# FAT32.net
KiCad netlist of a schematic drawn in Altium Designer
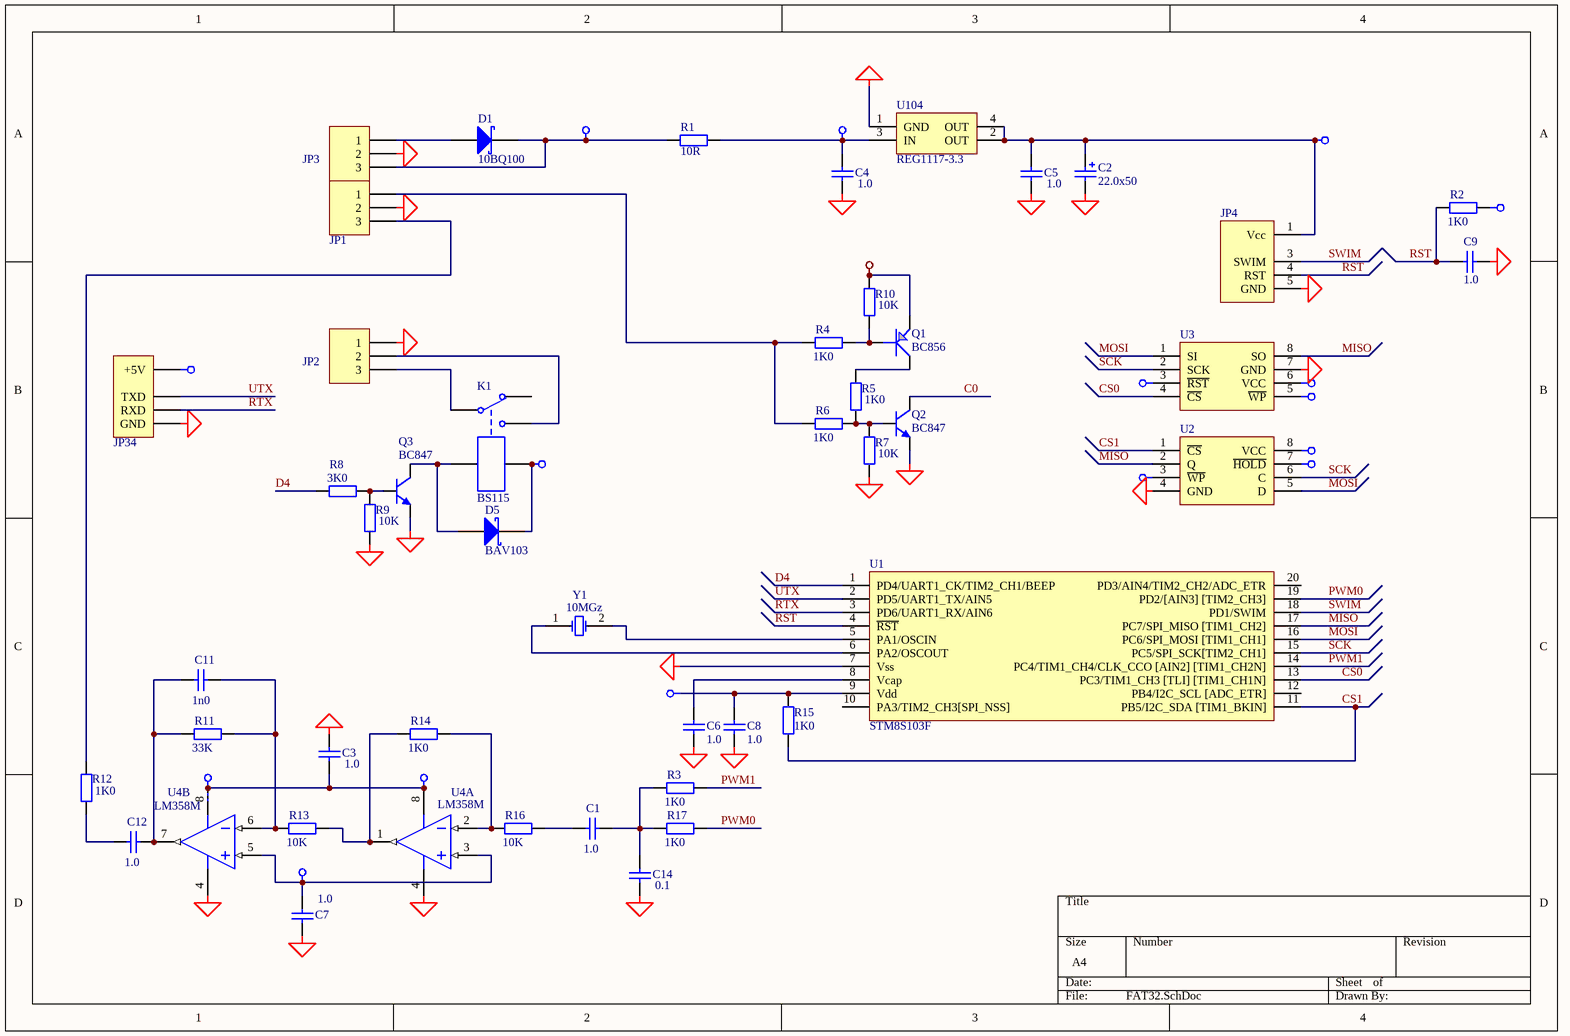
[diagram p0: FAT32.SchDoc]

(export (version "E")
  (design (tool "Eeschema 10.0.6"))
  (components
    (comp (ref "C1")
      (value "1.0")
      (footprint "_1206")
      (description "Capacitor (Semiconductor SIM Model)")
      (fields (field (name "MANUFACTURER") "Generic Components") (field (name "PUBLISHER") "Altium Limited"))
      (libsource (lib "Miscellaneous Devices") (part "Cap Semi"))
    )
    (comp (ref "C2")
      (value "22.0x50")
      (footprint "CAP_EL_6_3")
      (description "Polarized Capacitor (Radial)")
      (fields (field (name "MANUFACTURER") "Generic Components") (field (name "PUBLISHER") "Altium Limited"))
      (libsource (lib "PAL") (part "Cap Pol1"))
    )
    (comp (ref "C3")
      (value "1.0")
      (footprint "_1206")
      (description "Capacitor (Semiconductor SIM Model)")
      (fields (field (name "MANUFACTURER") "Generic Components") (field (name "PUBLISHER") "Altium Limited"))
      (libsource (lib "Miscellaneous Devices") (part "Cap Semi"))
    )
    (comp (ref "C4")
      (value "1.0")
      (footprint "_1206")
      (description "Capacitor (Semiconductor SIM Model)")
      (fields (field (name "MANUFACTURER") "Generic Components") (field (name "PUBLISHER") "Altium Limited"))
      (libsource (lib "Miscellaneous Devices") (part "Cap Semi"))
    )
    (comp (ref "C5")
      (value "1.0")
      (footprint "_1206")
      (description "Capacitor (Semiconductor SIM Model)")
      (fields (field (name "MANUFACTURER") "Generic Components") (field (name "PUBLISHER") "Altium Limited"))
      (libsource (lib "Miscellaneous Devices") (part "Cap Semi"))
    )
    (comp (ref "C6")
      (value "1.0")
      (footprint "_1206")
      (description "Capacitor (Semiconductor SIM Model)")
      (fields (field (name "MANUFACTURER") "Generic Components") (field (name "PUBLISHER") "Altium Limited"))
      (libsource (lib "Miscellaneous Devices") (part "Cap Semi"))
    )
    (comp (ref "C7")
      (value "1.0")
      (footprint "_1206")
      (description "Capacitor (Semiconductor SIM Model)")
      (fields (field (name "MANUFACTURER") "Generic Components") (field (name "PUBLISHER") "Altium Limited"))
      (libsource (lib "Miscellaneous Devices") (part "Cap Semi"))
    )
    (comp (ref "C8")
      (value "1.0")
      (footprint "_1206")
      (description "Capacitor (Semiconductor SIM Model)")
      (fields (field (name "MANUFACTURER") "Generic Components") (field (name "PUBLISHER") "Altium Limited"))
      (libsource (lib "Miscellaneous Devices") (part "Cap Semi"))
    )
    (comp (ref "C9")
      (value "1.0")
      (footprint "_1206")
      (description "Capacitor (Semiconductor SIM Model)")
      (fields (field (name "MANUFACTURER") "Generic Components") (field (name "PUBLISHER") "Altium Limited"))
      (libsource (lib "") (part "Cap Semi_1"))
    )
    (comp (ref "C11")
      (value "1n0")
      (footprint "_1206")
      (description "Capacitor (Semiconductor SIM Model)")
      (fields (field (name "MANUFACTURER") "Generic Components") (field (name "PUBLISHER") "Altium Limited"))
      (libsource (lib "") (part "Cap Semi_1"))
    )
    (comp (ref "C12")
      (value "1.0")
      (footprint "_1206")
      (description "Capacitor (Semiconductor SIM Model)")
      (fields (field (name "MANUFACTURER") "Generic Components") (field (name "PUBLISHER") "Altium Limited"))
      (libsource (lib "") (part "Cap Semi_1"))
    )
    (comp (ref "C14")
      (value "0.1")
      (footprint "_1206")
      (description "Capacitor (Semiconductor SIM Model)")
      (fields (field (name "MANUFACTURER") "Generic Components") (field (name "PUBLISHER") "Altium Limited"))
      (libsource (lib "Miscellaneous Devices") (part "Cap Semi"))
    )
    (comp (ref "D1")
      (value "10BQ100")
      (footprint "DSO-C2/X2.3")
      (description "Schottky Rectifier")
      (fields
        (field (name "MANUFACTURER") "International Rectifier")
        (field (name "PUBLISHER") "Altium Limited")
      )
      (libsource (lib "IR Discrete Diode") (part "10BQ015"))
    )
    (comp (ref "D5")
      (value "BAV103")
      (footprint "_1206d")
      (description "Schottky Rectifier")
      (fields
        (field (name "MANUFACTURER") "International Rectifier")
        (field (name "PUBLISHER") "Altium Limited")
      )
      (libsource (lib "IR Discrete Diode") (part "10BQ015"))
    )
    (comp (ref "JP1")
      (value "Header 3")
      (footprint "BT5-3")
      (description "Header, 3-Pin")
      (fields (field (name "MANUFACTURER") "Generic Components") (field (name "PUBLISHER") "Altium Limited"))
      (libsource (lib "Miscellaneous Connectors") (part "Header 3"))
    )
    (comp (ref "JP2")
      (value "Header 3")
      (footprint "BT5-3")
      (description "Header, 3-Pin")
      (fields (field (name "MANUFACTURER") "Generic Components") (field (name "PUBLISHER") "Altium Limited"))
      (libsource (lib "Miscellaneous Connectors") (part "Header 3"))
    )
    (comp (ref "JP3")
      (value "Header 3")
      (footprint "BT5-3")
      (description "Header, 3-Pin")
      (fields (field (name "MANUFACTURER") "Generic Components") (field (name "PUBLISHER") "Altium Limited"))
      (libsource (lib "Miscellaneous Connectors") (part "Header 3"))
    )
    (comp (ref "JP4") (value "~") (footprint "HDR1X5_uart") (libsource (lib "PAL") (part "SWIM_CONN")))
    (comp (ref "JP34")
      (value "UART_PORT")
      (footprint "HDR1X5_uart")
      (description "Header, 5-Pin")
      (fields (field (name "MANUFACTURER") "Generic Components") (field (name "PUBLISHER") "Altium Limited"))
      (libsource (lib "igorenja") (part "UART_PORT"))
    )
    (comp (ref "K1")
      (value "BS115")
      (footprint "BS115")
      (description "Single-Pole Dual-Throw Relay")
      (fields (field (name "MANUFACTURER") "Generic Components") (field (name "PUBLISHER") "Altium Limited"))
      (libsource (lib "PAL") (part "BS115"))
    )
    (comp (ref "Q1") (value "BC856") (footprint "SO-G3") (libsource (lib "MAIN") (part "GT109")))
    (comp (ref "Q2")
      (value "BC847")
      (footprint "SO-G3/C2.5")
      (description "General Purpose Transistor NPN Silicon")
      (fields (field (name "MANUFACTURER") "Motorola") (field (name "PUBLISHER") "Altium Limited"))
      (libsource (lib "PAL") (part "BC847ALT1"))
    )
    (comp (ref "Q3")
      (value "BC847")
      (footprint "SO-G3/C2.5")
      (description "General Purpose Transistor NPN Silicon")
      (fields (field (name "MANUFACTURER") "Motorola") (field (name "PUBLISHER") "Altium Limited"))
      (libsource (lib "PAL") (part "BC847ALT1"))
    )
    (comp (ref "R1")
      (value "Res2")
      (footprint "_1206")
      (description "Resistor")
      (fields
        (field (name "MANUFACTURER") "Generic Components")
        (field (name "ALTIUM_VALUE") "10R")
        (field (name "PUBLISHER") "Altium Limited")
      )
      (libsource (lib "") (part "Res2_1"))
    )
    (comp (ref "R2")
      (value "1K0")
      (footprint "_1206")
      (description "Resistor")
      (fields (field (name "MANUFACTURER") "Generic Components") (field (name "PUBLISHER") "Altium Limited"))
      (libsource (lib "") (part "Res2_3"))
    )
    (comp (ref "R3")
      (value "1K0")
      (footprint "_1206")
      (description "Resistor")
      (fields (field (name "MANUFACTURER") "Generic Components") (field (name "PUBLISHER") "Altium Limited"))
      (libsource (lib "Miscellaneous Devices") (part "Res2"))
    )
    (comp (ref "R4")
      (value "1K0")
      (footprint "_1206")
      (description "Resistor")
      (fields (field (name "MANUFACTURER") "Generic Components") (field (name "PUBLISHER") "Altium Limited"))
      (libsource (lib "") (part "Res2_3"))
    )
    (comp (ref "R5")
      (value "1K0")
      (footprint "_1206")
      (description "Resistor")
      (fields (field (name "MANUFACTURER") "Generic Components") (field (name "PUBLISHER") "Altium Limited"))
      (libsource (lib "") (part "Res2_5"))
    )
    (comp (ref "R6")
      (value "1K0")
      (footprint "_1206")
      (description "Resistor")
      (fields (field (name "MANUFACTURER") "Generic Components") (field (name "PUBLISHER") "Altium Limited"))
      (libsource (lib "") (part "Res2_3"))
    )
    (comp (ref "R7")
      (value "10K")
      (footprint "_1206")
      (description "Resistor")
      (fields (field (name "MANUFACTURER") "Generic Components") (field (name "PUBLISHER") "Altium Limited"))
      (libsource (lib "") (part "Res2_2"))
    )
    (comp (ref "R8")
      (value "3K0")
      (footprint "_1206")
      (description "Resistor")
      (fields (field (name "MANUFACTURER") "Generic Components") (field (name "PUBLISHER") "Altium Limited"))
      (libsource (lib "") (part "Res2_3"))
    )
    (comp (ref "R9")
      (value "10K")
      (footprint "_1206")
      (description "Resistor")
      (fields (field (name "MANUFACTURER") "Generic Components") (field (name "PUBLISHER") "Altium Limited"))
      (libsource (lib "") (part "Res2_2"))
    )
    (comp (ref "R10")
      (value "10K")
      (footprint "_1206")
      (description "Resistor")
      (fields (field (name "MANUFACTURER") "Generic Components") (field (name "PUBLISHER") "Altium Limited"))
      (libsource (lib "PAL") (part "RES"))
    )
    (comp (ref "R11")
      (value "33K")
      (footprint "_1206")
      (description "Resistor")
      (fields (field (name "MANUFACTURER") "Generic Components") (field (name "PUBLISHER") "Altium Limited"))
      (libsource (lib "Miscellaneous Devices") (part "Res2"))
    )
    (comp (ref "R12")
      (value "1K0")
      (footprint "_1206")
      (description "Resistor")
      (fields (field (name "MANUFACTURER") "Generic Components") (field (name "PUBLISHER") "Altium Limited"))
      (libsource (lib "") (part "Res2_5"))
    )
    (comp (ref "R13")
      (value "10K")
      (footprint "_1206")
      (description "Resistor")
      (fields (field (name "MANUFACTURER") "Generic Components") (field (name "PUBLISHER") "Altium Limited"))
      (libsource (lib "Miscellaneous Devices") (part "Res2"))
    )
    (comp (ref "R14")
      (value "1K0")
      (footprint "_1206")
      (description "Resistor")
      (fields (field (name "MANUFACTURER") "Generic Components") (field (name "PUBLISHER") "Altium Limited"))
      (libsource (lib "Miscellaneous Devices") (part "Res2"))
    )
    (comp (ref "R15")
      (value "1K0")
      (footprint "_1206")
      (description "Resistor")
      (fields (field (name "MANUFACTURER") "Generic Components") (field (name "PUBLISHER") "Altium Limited"))
      (libsource (lib "") (part "Res2_4"))
    )
    (comp (ref "R16")
      (value "10K")
      (footprint "_1206")
      (description "Resistor")
      (fields (field (name "MANUFACTURER") "Generic Components") (field (name "PUBLISHER") "Altium Limited"))
      (libsource (lib "Miscellaneous Devices") (part "Res2"))
    )
    (comp (ref "R17")
      (value "1K0")
      (footprint "_1206")
      (description "Resistor")
      (fields (field (name "MANUFACTURER") "Generic Components") (field (name "PUBLISHER") "Altium Limited"))
      (libsource (lib "Miscellaneous Devices") (part "Res2"))
    )
    (comp (ref "U1") (value "~") (footprint "TSSO6x6-G20/Y1.6") (libsource (lib "PAL") (part "STM8S103F")))
    (comp (ref "U2") (value "~") (footprint "SO-G8") (libsource (lib "PAL") (part "M25P10")))
    (comp (ref "U3") (value "~") (footprint "AT45W") (libsource (lib "PAL") (part "AT45DB161D-SU")))
    (comp (ref "U4")
      (value "LM358M")
      (footprint "SO-G8")
      (description "Low-Power Dual Operational Amplifier")
      (fields
        (field (name "MANUFACTURER") "National Semiconductor")
        (field (name "PUBLISHER") "Altium Limited")
      )
      (libsource (lib "NSC Operational Amplifier") (part "LM358M"))
    )
    (comp (ref "U104")
      (value "REG1117-3.3")
      (footprint "SIP-G3/C7.4")
      (description "800mA and 1A Low Dropout Positive Regulator 2.85V, 3.3V, 5V, and Adjustable")
      (fields (field (name "MANUFACTURER") "Burr-Brown") (field (name "PUBLISHER") "Altium Limited"))
      (libsource (lib "BB Power Mgt Voltage Regulator") (part "REG1117-3.3"))
    )
    (comp (ref "Y1")
      (value "10MGz")
      (footprint "QWARZ1")
      (description "Crystal Oscillator")
      (fields (field (name "MANUFACTURER") "Generic Components") (field (name "PUBLISHER") "Altium Limited"))
      (libsource (lib "Miscellaneous Devices") (part "XTAL"))
    )
  )
  (nets
    (net (code "1") (name "+3v3") (class "Default")
      (node (ref "C2") (pin "1") (pinfunction "1_1") (pintype "passive"))
      (node (ref "C5") (pin "2") (pinfunction "2_2") (pintype "passive"))
      (node (ref "C7") (pin "2") (pinfunction "2_2") (pintype "passive"))
      (node (ref "C8") (pin "2") (pinfunction "2_2") (pintype "passive"))
      (node (ref "JP34") (pin "1") (pinfunction "+5V_1") (pintype "passive"))
      (node (ref "JP4") (pin "1") (pinfunction "Vcc_1") (pintype "passive"))
      (node (ref "R15") (pin "2") (pinfunction "2_2") (pintype "passive"))
      (node (ref "R2") (pin "1") (pinfunction "1_1") (pintype "passive"))
      (node (ref "U1") (pin "9") (pinfunction "Vdd_9") (pintype "passive"))
      (node (ref "U104") (pin "2") (pinfunction "OUT_2") (pintype "power_in"))
      (node (ref "U104") (pin "4") (pinfunction "OUT_4") (pintype "power_in"))
      (node (ref "U2") (pin "3") (pinfunction "~{WP}_3") (pintype "passive"))
      (node (ref "U2") (pin "7") (pinfunction "~{HOLD}_7") (pintype "passive"))
      (node (ref "U2") (pin "8") (pinfunction "VCC_8") (pintype "passive"))
      (node (ref "U3") (pin "3") (pinfunction "~{RST}_3") (pintype "passive"))
      (node (ref "U3") (pin "5") (pinfunction "~{WP}_5") (pintype "passive"))
      (node (ref "U3") (pin "6") (pinfunction "VCC_6") (pintype "passive"))
      (node (ref "U4") (pin "3") (pinfunction "IN+_3") (pintype "input"))
      (node (ref "U4") (pin "5") (pinfunction "IN+_5") (pintype "input"))
    )
    (net (code "2") (name "+12v") (class "Default")
      (node (ref "D1") (pin "2") (pinfunction "K_2") (pintype "passive"))
      (node (ref "D5") (pin "2") (pinfunction "K_2") (pintype "passive"))
      (node (ref "JP3") (pin "3") (pinfunction "3_3") (pintype "passive"))
      (node (ref "K1") (pin "5") (pinfunction "5_5") (pintype "passive"))
      (node (ref "Q1") (pin "2") (pinfunction "E_2") (pintype "passive"))
      (node (ref "R1") (pin "1") (pinfunction "1_1") (pintype "passive"))
      (node (ref "R10") (pin "2") (pinfunction "2_2") (pintype "passive"))
    )
    (net (code "3") (name "+12vi") (class "Default")
      (node (ref "C3") (pin "2") (pinfunction "2_2") (pintype "passive"))
      (node (ref "C4") (pin "2") (pinfunction "2_2") (pintype "passive"))
      (node (ref "R1") (pin "2") (pinfunction "2_2") (pintype "passive"))
      (node (ref "U104") (pin "3") (pinfunction "IN_3") (pintype "power_in"))
      (node (ref "U4") (pin "8") (pinfunction "V+_8") (pintype "power_in"))
    )
    (net (code "4") (name "/C0") (class "Default")
      (node (ref "Q2") (pin "3") (pinfunction "C_3") (pintype "passive"))
    )
    (net (code "5") (name "/CS0") (class "Default")
      (node (ref "U1") (pin "13") (pinfunction "PC3/TIM1_CH3_[TLI]_[TIM1_CH1N]_13") (pintype "passive"))
      (node (ref "U3") (pin "4") (pinfunction "~{CS}_4") (pintype "passive"))
    )
    (net (code "6") (name "/CS1") (class "Default")
      (node (ref "R15") (pin "1") (pinfunction "1_1") (pintype "passive"))
      (node (ref "U1") (pin "11") (pinfunction "PB5/I2C_SDA_[TIM1_BKIN]_11") (pintype "passive"))
      (node (ref "U2") (pin "1") (pinfunction "~{CS}_1") (pintype "passive"))
    )
    (net (code "7") (name "/D4") (class "Default")
      (node (ref "R8") (pin "2") (pinfunction "2_2") (pintype "passive"))
      (node (ref "U1") (pin "1") (pinfunction "PD4/UART1_CK/TIM2_CH1/BEEP_1") (pintype "passive"))
    )
    (net (code "8") (name "/MISO") (class "Default")
      (node (ref "U1") (pin "17") (pinfunction "PC7/SPI_MISO_[TIM1_CH2]_17") (pintype "passive"))
      (node (ref "U2") (pin "2") (pinfunction "Q_2") (pintype "passive"))
      (node (ref "U3") (pin "8") (pinfunction "SO_8") (pintype "passive"))
    )
    (net (code "9") (name "/MOSI") (class "Default")
      (node (ref "U1") (pin "16") (pinfunction "PC6/SPI_MOSI_[TIM1_CH1]_16") (pintype "passive"))
      (node (ref "U2") (pin "5") (pinfunction "D_5") (pintype "passive"))
      (node (ref "U3") (pin "1") (pinfunction "SI_1") (pintype "passive"))
    )
    (net (code "10") (name "/PWM0") (class "Default")
      (node (ref "R17") (pin "2") (pinfunction "2_2") (pintype "passive"))
      (node (ref "U1") (pin "19") (pinfunction "PD2/[AIN3]_[TIM2_CH3]_19") (pintype "passive"))
    )
    (net (code "11") (name "/PWM1") (class "Default")
      (node (ref "R3") (pin "2") (pinfunction "2_2") (pintype "passive"))
      (node (ref "U1") (pin "14") (pinfunction "PC4/TIM1_CH4/CLK_CCO_[AIN2]_[TIM1_CH2N]_14") (pintype "passive"))
    )
    (net (code "12") (name "/RST") (class "Default")
      (node (ref "C9") (pin "2") (pinfunction "2_2") (pintype "passive"))
      (node (ref "JP4") (pin "4") (pinfunction "RST_4") (pintype "passive"))
      (node (ref "R2") (pin "2") (pinfunction "2_2") (pintype "passive"))
      (node (ref "U1") (pin "4") (pinfunction "~{RST}_4") (pintype "passive"))
    )
    (net (code "13") (name "/RTX") (class "Default")
      (node (ref "JP34") (pin "4") (pinfunction "RXD_4") (pintype "passive"))
      (node (ref "U1") (pin "3") (pinfunction "PD6/UART1_RX/AIN6_3") (pintype "passive"))
    )
    (net (code "14") (name "/SCK") (class "Default")
      (node (ref "U1") (pin "15") (pinfunction "PC5/SPI_SCK[TIM2_CH1]_15") (pintype "passive"))
      (node (ref "U2") (pin "6") (pinfunction "C_6") (pintype "passive"))
      (node (ref "U3") (pin "2") (pinfunction "SCK_2") (pintype "passive"))
    )
    (net (code "15") (name "/SWIM") (class "Default")
      (node (ref "JP4") (pin "3") (pinfunction "SWIM_3") (pintype "passive"))
      (node (ref "U1") (pin "18") (pinfunction "PD1/SWIM_18") (pintype "passive"))
    )
    (net (code "16") (name "/UTX") (class "Default")
      (node (ref "JP34") (pin "3") (pinfunction "TXD_3") (pintype "passive"))
      (node (ref "U1") (pin "2") (pinfunction "PD5/UART1_TX/AIN5_2") (pintype "passive"))
    )
    (net (code "17") (name "GND") (class "Default")
      (node (ref "C14") (pin "2") (pinfunction "2_2") (pintype "passive"))
      (node (ref "C2") (pin "2") (pinfunction "2_2") (pintype "passive"))
      (node (ref "C3") (pin "1") (pinfunction "1_1") (pintype "passive"))
      (node (ref "C4") (pin "1") (pinfunction "1_1") (pintype "passive"))
      (node (ref "C5") (pin "1") (pinfunction "1_1") (pintype "passive"))
      (node (ref "C6") (pin "1") (pinfunction "1_1") (pintype "passive"))
      (node (ref "C7") (pin "1") (pinfunction "1_1") (pintype "passive"))
      (node (ref "C8") (pin "1") (pinfunction "1_1") (pintype "passive"))
      (node (ref "C9") (pin "1") (pinfunction "1_1") (pintype "passive"))
      (node (ref "JP1") (pin "2") (pinfunction "2_2") (pintype "passive"))
      (node (ref "JP2") (pin "1") (pinfunction "1_1") (pintype "passive"))
      (node (ref "JP3") (pin "2") (pinfunction "2_2") (pintype "passive"))
      (node (ref "JP34") (pin "5") (pinfunction "GND_5") (pintype "passive"))
      (node (ref "JP4") (pin "5") (pinfunction "GND_5") (pintype "passive"))
      (node (ref "Q2") (pin "2") (pinfunction "E_2") (pintype "passive"))
      (node (ref "Q3") (pin "2") (pinfunction "E_2") (pintype "passive"))
      (node (ref "R7") (pin "2") (pinfunction "2_2") (pintype "passive"))
      (node (ref "R9") (pin "2") (pinfunction "2_2") (pintype "passive"))
      (node (ref "U1") (pin "7") (pinfunction "Vss_7") (pintype "passive"))
      (node (ref "U104") (pin "1") (pinfunction "GND_1") (pintype "power_in"))
      (node (ref "U2") (pin "4") (pinfunction "GND_4") (pintype "passive"))
      (node (ref "U3") (pin "7") (pinfunction "GND_7") (pintype "passive"))
      (node (ref "U4") (pin "4") (pinfunction "GND_4") (pintype "power_in"))
    )
    (net (code "18") (name "Net-(C1-Pad1)") (class "Default")
      (node (ref "C1") (pin "1") (pinfunction "1_1") (pintype "passive"))
      (node (ref "R16") (pin "2") (pinfunction "2_2") (pintype "passive"))
    )
    (net (code "19") (name "Net-(C1-Pad2)") (class "Default")
      (node (ref "C1") (pin "2") (pinfunction "2_2") (pintype "passive"))
      (node (ref "C14") (pin "1") (pinfunction "1_1") (pintype "passive"))
      (node (ref "R17") (pin "1") (pinfunction "1_1") (pintype "passive"))
      (node (ref "R3") (pin "1") (pinfunction "1_1") (pintype "passive"))
    )
    (net (code "20") (name "Net-(C12-Pad2)") (class "Default")
      (node (ref "C12") (pin "2") (pinfunction "2_2") (pintype "passive"))
      (node (ref "R12") (pin "2") (pinfunction "2_2") (pintype "passive"))
    )
    (net (code "21") (name "Net-(D1-A)") (class "Default")
      (node (ref "D1") (pin "1") (pinfunction "A_1") (pintype "passive"))
      (node (ref "JP3") (pin "1") (pinfunction "1_1") (pintype "passive"))
    )
    (net (code "22") (name "Net-(D5-A)") (class "Default")
      (node (ref "D5") (pin "1") (pinfunction "A_1") (pintype "passive"))
      (node (ref "K1") (pin "4") (pinfunction "4_4") (pintype "passive"))
      (node (ref "Q3") (pin "3") (pinfunction "C_3") (pintype "passive"))
    )
    (net (code "23") (name "Net-(JP1-Pad1)") (class "Default")
      (node (ref "JP1") (pin "1") (pinfunction "1_1") (pintype "passive"))
      (node (ref "R4") (pin "2") (pinfunction "2_2") (pintype "passive"))
      (node (ref "R6") (pin "2") (pinfunction "2_2") (pintype "passive"))
    )
    (net (code "24") (name "Net-(JP1-Pad3)") (class "Default")
      (node (ref "JP1") (pin "3") (pinfunction "3_3") (pintype "passive"))
      (node (ref "R12") (pin "1") (pinfunction "1_1") (pintype "passive"))
    )
    (net (code "25") (name "Net-(JP2-Pad2)") (class "Default")
      (node (ref "JP2") (pin "2") (pinfunction "2_2") (pintype "passive"))
      (node (ref "K1") (pin "3") (pinfunction "3_3") (pintype "passive"))
    )
    (net (code "26") (name "Net-(JP2-Pad3)") (class "Default")
      (node (ref "JP2") (pin "3") (pinfunction "3_3") (pintype "passive"))
      (node (ref "K1") (pin "1") (pinfunction "1_1") (pintype "passive"))
    )
    (net (code "27") (name "Net-(Q1-B)") (class "Default")
      (node (ref "Q1") (pin "1") (pinfunction "B_1") (pintype "passive"))
      (node (ref "R10") (pin "1") (pinfunction "1_1") (pintype "passive"))
      (node (ref "R4") (pin "1") (pinfunction "1_1") (pintype "passive"))
    )
    (net (code "28") (name "Net-(Q1-C)") (class "Default")
      (node (ref "Q1") (pin "3") (pinfunction "C_3") (pintype "passive"))
      (node (ref "R5") (pin "1") (pinfunction "1_1") (pintype "passive"))
    )
    (net (code "29") (name "Net-(Q2-B)") (class "Default")
      (node (ref "Q2") (pin "1") (pinfunction "B_1") (pintype "passive"))
      (node (ref "R5") (pin "2") (pinfunction "2_2") (pintype "passive"))
      (node (ref "R6") (pin "1") (pinfunction "1_1") (pintype "passive"))
      (node (ref "R7") (pin "1") (pinfunction "1_1") (pintype "passive"))
    )
    (net (code "30") (name "Net-(Q3-B)") (class "Default")
      (node (ref "Q3") (pin "1") (pinfunction "B_1") (pintype "passive"))
      (node (ref "R8") (pin "1") (pinfunction "1_1") (pintype "passive"))
      (node (ref "R9") (pin "1") (pinfunction "1_1") (pintype "passive"))
    )
    (net (code "31") (name "Net-(U1-PA1{slash}OSCIN)") (class "Default")
      (node (ref "U1") (pin "5") (pinfunction "PA1/OSCIN_5") (pintype "passive"))
      (node (ref "Y1") (pin "2") (pinfunction "OSC2_2") (pintype "passive"))
    )
    (net (code "32") (name "Net-(U1-PA2{slash}OSCOUT)") (class "Default")
      (node (ref "U1") (pin "6") (pinfunction "PA2/OSCOUT_6") (pintype "passive"))
      (node (ref "Y1") (pin "1") (pinfunction "OSC1_1") (pintype "passive"))
    )
    (net (code "33") (name "Net-(U1-Vcap)") (class "Default")
      (node (ref "C6") (pin "2") (pinfunction "2_2") (pintype "passive"))
      (node (ref "U1") (pin "8") (pinfunction "Vcap_8") (pintype "passive"))
    )
    (net (code "34") (name "Net-(U4A-IN-)") (class "Default")
      (node (ref "R14") (pin "2") (pinfunction "2_2") (pintype "passive"))
      (node (ref "R16") (pin "1") (pinfunction "1_1") (pintype "passive"))
      (node (ref "U4") (pin "2") (pinfunction "IN-_2") (pintype "input"))
    )
    (net (code "35") (name "Net-(U4A-OUT)") (class "Default")
      (node (ref "R13") (pin "2") (pinfunction "2_2") (pintype "passive"))
      (node (ref "R14") (pin "1") (pinfunction "1_1") (pintype "passive"))
      (node (ref "U4") (pin "1") (pinfunction "OUT_1") (pintype "output"))
    )
    (net (code "36") (name "Net-(U4B-IN-)") (class "Default")
      (node (ref "C11") (pin "2") (pinfunction "2_2") (pintype "passive"))
      (node (ref "R11") (pin "2") (pinfunction "2_2") (pintype "passive"))
      (node (ref "R13") (pin "1") (pinfunction "1_1") (pintype "passive"))
      (node (ref "U4") (pin "6") (pinfunction "IN-_6") (pintype "input"))
    )
    (net (code "37") (name "Net-(U4B-OUT)") (class "Default")
      (node (ref "C11") (pin "1") (pinfunction "1_1") (pintype "passive"))
      (node (ref "C12") (pin "1") (pinfunction "1_1") (pintype "passive"))
      (node (ref "R11") (pin "1") (pinfunction "1_1") (pintype "passive"))
      (node (ref "U4") (pin "7") (pinfunction "OUT_7") (pintype "output"))
    )
    (net (code "38") (name "unconnected-(K1-Pad2)") (class "Default")
      (node (ref "K1") (pin "2") (pinfunction "2_2") (pintype "passive"))
    )
    (net (code "39") (name "unconnected-(U1-PA3{slash}TIM2_CH3[SPI_NSS]-Pad10)") (class "Default")
      (node (ref "U1") (pin "10") (pinfunction "PA3/TIM2_CH3[SPI_NSS]_10") (pintype "passive"))
    )
    (net (code "40") (name "unconnected-(U1-PB4{slash}I2C_SCL_[ADC_ETR]-Pad12)") (class "Default")
      (node (ref "U1") (pin "12") (pinfunction "PB4/I2C_SCL_[ADC_ETR]_12") (pintype "passive"))
    )
    (net (code "41") (name "unconnected-(U1-PD3{slash}AIN4{slash}TIM2_CH2{slash}ADC_ETR-Pad20)") (class "Default")
      (node (ref "U1") (pin "20") (pinfunction "PD3/AIN4/TIM2_CH2/ADC_ETR_20") (pintype "passive"))
    )
  )
)
